# untitled.net
KiCad netlist of a schematic drawn in EAGLE
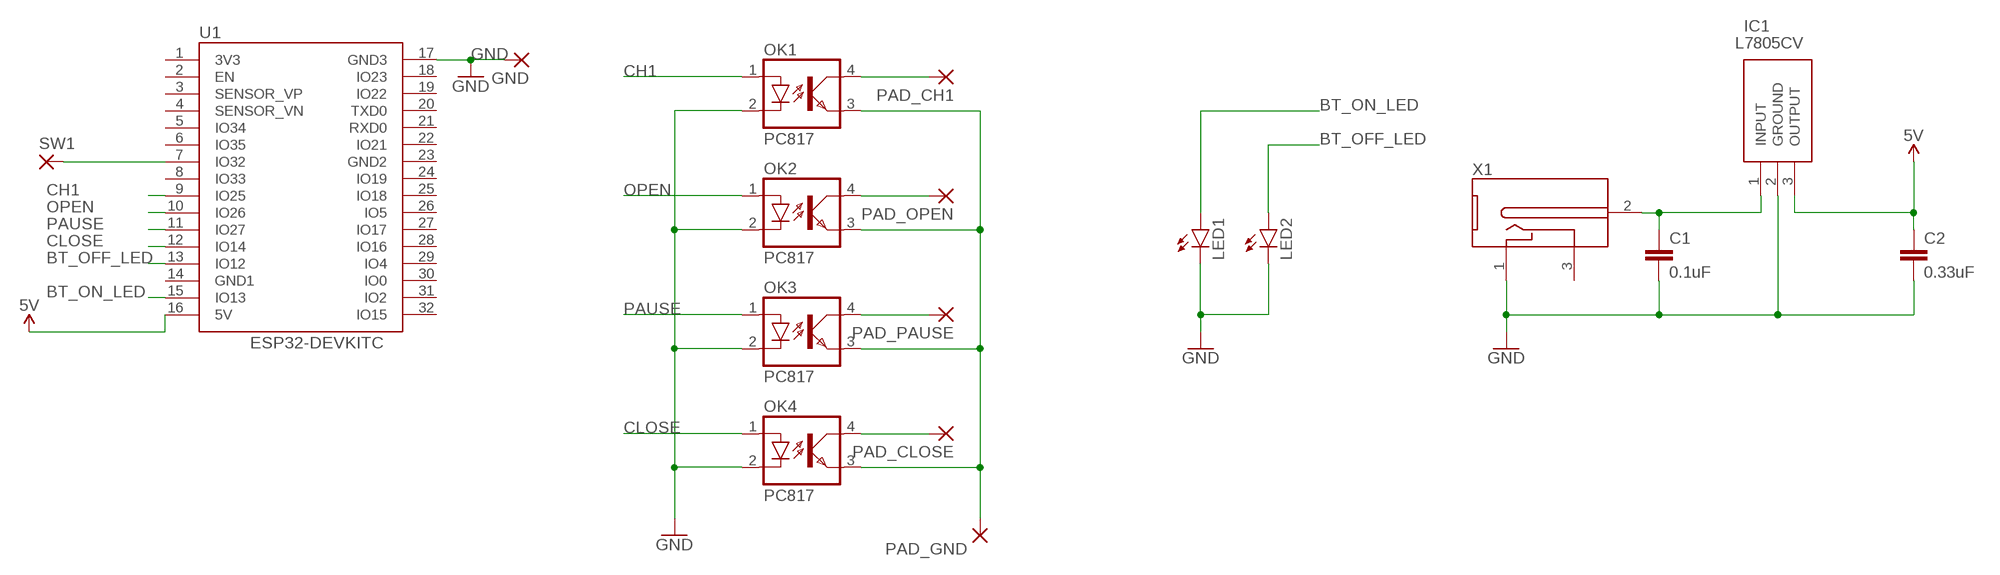
[diagram p0: schematic, sheet 1]

(export (version "E")
  (design (tool "Eeschema 10.0.6"))
  (components
    (comp (ref "C1")
      (value "0.1uF")
      (footprint "eagle-import:C2.5-2")
      (libsource (lib "eagle-import") (part "C2.5/2"))
    )
    (comp (ref "C2")
      (value "0.33uF")
      (footprint "eagle-import:C2.5-2")
      (libsource (lib "eagle-import") (part "C2.5/2"))
    )
    (comp (ref "GND")
      (value "2,54/1,0")
      (footprint "eagle-import:2,54_1,0")
      (libsource (lib "eagle-import") (part "2,54/1,0"))
    )
    (comp (ref "IC1")
      (value "L7805CV")
      (footprint "eagle-import:TO255P460X1020X2008-3P")
      (fields (field (name "MOUSER_PART_NUMBER") "511-L7805CV"))
      (libsource (lib "eagle-import") (part "L7805CV"))
    )
    (comp (ref "LED1")
      (value "LED5MM")
      (footprint "eagle-import:LED5MM")
      (libsource (lib "eagle-import") (part "LED5MM"))
    )
    (comp (ref "LED2")
      (value "LED5MM")
      (footprint "eagle-import:LED5MM")
      (libsource (lib "eagle-import") (part "LED5MM"))
    )
    (comp (ref "OK1")
      (value "PC817")
      (footprint "eagle-import:DIL04")
      (fields (field (name "MPN") "PC817X4J000F"))
      (libsource (lib "eagle-import") (part "PC817"))
    )
    (comp (ref "OK2")
      (value "PC817")
      (footprint "eagle-import:DIL04")
      (fields (field (name "MPN") "PC817X4J000F"))
      (libsource (lib "eagle-import") (part "PC817"))
    )
    (comp (ref "OK3")
      (value "PC817")
      (footprint "eagle-import:DIL04")
      (fields (field (name "MPN") "PC817X4J000F"))
      (libsource (lib "eagle-import") (part "PC817"))
    )
    (comp (ref "OK4")
      (value "PC817")
      (footprint "eagle-import:DIL04")
      (fields (field (name "MPN") "PC817X4J000F"))
      (libsource (lib "eagle-import") (part "PC817"))
    )
    (comp (ref "PAD_CH1")
      (value "2,54/1,0")
      (footprint "eagle-import:2,54_1,0")
      (libsource (lib "eagle-import") (part "2,54/1,0"))
    )
    (comp (ref "PAD_CLOSE")
      (value "2,54/1,0")
      (footprint "eagle-import:2,54_1,0")
      (libsource (lib "eagle-import") (part "2,54/1,0"))
    )
    (comp (ref "PAD_GND")
      (value "2,54/1,0")
      (footprint "eagle-import:2,54_1,0")
      (libsource (lib "eagle-import") (part "2,54/1,0"))
    )
    (comp (ref "PAD_OPEN")
      (value "2,54/1,0")
      (footprint "eagle-import:2,54_1,0")
      (libsource (lib "eagle-import") (part "2,54/1,0"))
    )
    (comp (ref "PAD_PAUSE")
      (value "2,54/1,0")
      (footprint "eagle-import:2,54_1,0")
      (libsource (lib "eagle-import") (part "2,54/1,0"))
    )
    (comp (ref "SW1")
      (value "2,54/1,0")
      (footprint "eagle-import:2,54_1,0")
      (libsource (lib "eagle-import") (part "2,54/1,0"))
    )
    (comp (ref "U1")
      (value "ESP32-DEVKITC")
      (footprint "eagle-import:MODULE_ESP32-DEVKITC")
      (fields (field (name "MF") "Espressif Systems"))
      (libsource (lib "eagle-import") (part "ESP32-DEVKITC"))
    )
    (comp (ref "X1")
      (value "DC-2.1MM-5MM")
      (footprint "eagle-import:DC-21MM")
      (libsource (lib "eagle-import") (part "DC-5MM-2.1MM"))
    )
  )
  (nets
    (net (code "1") (name "/2") (class "Default")
      (node (ref "X1") (pin "3") (pinfunction "2_3") (pintype "power_in"))
    )
    (net (code "2") (name "/3V3") (class "Default")
      (node (ref "U1") (pin "1") (pinfunction "3V3_1") (pintype "power_in"))
    )
    (net (code "3") (name "/BT_OFF_LED") (class "Default")
      (node (ref "LED2") (pin "A") (pinfunction "A_A") (pintype "passive"))
      (node (ref "U1") (pin "13") (pinfunction "IO12_13") (pintype "bidirectional"))
    )
    (net (code "4") (name "/BT_ON_LED") (class "Default")
      (node (ref "LED1") (pin "A") (pinfunction "A_A") (pintype "passive"))
      (node (ref "U1") (pin "15") (pinfunction "IO13_15") (pintype "bidirectional"))
    )
    (net (code "5") (name "/CH1") (class "Default")
      (node (ref "OK1") (pin "1") (pinfunction "A_1") (pintype "passive"))
      (node (ref "U1") (pin "9") (pinfunction "IO25_9") (pintype "bidirectional"))
    )
    (net (code "6") (name "/CLOSE") (class "Default")
      (node (ref "OK4") (pin "1") (pinfunction "A_1") (pintype "passive"))
      (node (ref "U1") (pin "12") (pinfunction "IO14_12") (pintype "bidirectional"))
    )
    (net (code "7") (name "/GND1") (class "Default")
      (node (ref "U1") (pin "14") (pinfunction "GND1_14") (pintype "power_in"))
    )
    (net (code "8") (name "/GND2") (class "Default")
      (node (ref "U1") (pin "23") (pinfunction "GND2_23") (pintype "power_in"))
    )
    (net (code "9") (name "/OPEN") (class "Default")
      (node (ref "OK2") (pin "1") (pinfunction "A_1") (pintype "passive"))
      (node (ref "U1") (pin "10") (pinfunction "IO26_10") (pintype "bidirectional"))
    )
    (net (code "10") (name "/PAUSE") (class "Default")
      (node (ref "OK3") (pin "1") (pinfunction "A_1") (pintype "passive"))
      (node (ref "U1") (pin "11") (pinfunction "IO27_11") (pintype "bidirectional"))
    )
    (net (code "11") (name "5V") (class "Default")
      (node (ref "C2") (pin "1") (pinfunction "1_1") (pintype "passive"))
      (node (ref "IC1") (pin "3") (pinfunction "OUTPUT_3") (pintype "bidirectional"))
      (node (ref "U1") (pin "16") (pinfunction "5V_16") (pintype "bidirectional"))
    )
    (net (code "12") (name "GND") (class "Default")
      (node (ref "C1") (pin "2") (pinfunction "2_2") (pintype "passive"))
      (node (ref "C2") (pin "2") (pinfunction "2_2") (pintype "passive"))
      (node (ref "GND") (pin "1") (pinfunction "P_1") (pintype "passive"))
      (node (ref "IC1") (pin "2") (pinfunction "GROUND_2") (pintype "bidirectional"))
      (node (ref "LED1") (pin "K") (pinfunction "C_K") (pintype "passive"))
      (node (ref "LED2") (pin "K") (pinfunction "C_K") (pintype "passive"))
      (node (ref "OK1") (pin "2") (pinfunction "C_2") (pintype "passive"))
      (node (ref "OK2") (pin "2") (pinfunction "C_2") (pintype "passive"))
      (node (ref "OK3") (pin "2") (pinfunction "C_2") (pintype "passive"))
      (node (ref "OK4") (pin "2") (pinfunction "C_2") (pintype "passive"))
      (node (ref "U1") (pin "17") (pinfunction "GND3_17") (pintype "power_in"))
      (node (ref "X1") (pin "1") (pinfunction "1_1") (pintype "power_in"))
    )
    (net (code "13") (name "Net-(IC1-INPUT)") (class "Default")
      (node (ref "C1") (pin "1") (pinfunction "1_1") (pintype "passive"))
      (node (ref "IC1") (pin "1") (pinfunction "INPUT_1") (pintype "bidirectional"))
      (node (ref "X1") (pin "2") (pinfunction "3_2") (pintype "power_in"))
    )
    (net (code "14") (name "Net-(OK1-COL)") (class "Default")
      (node (ref "OK1") (pin "4") (pinfunction "COL_4") (pintype "passive"))
      (node (ref "PAD_CH1") (pin "1") (pinfunction "P_1") (pintype "passive"))
    )
    (net (code "15") (name "Net-(OK1-EMIT)") (class "Default")
      (node (ref "OK1") (pin "3") (pinfunction "EMIT_3") (pintype "passive"))
      (node (ref "OK2") (pin "3") (pinfunction "EMIT_3") (pintype "passive"))
      (node (ref "OK3") (pin "3") (pinfunction "EMIT_3") (pintype "passive"))
      (node (ref "OK4") (pin "3") (pinfunction "EMIT_3") (pintype "passive"))
      (node (ref "PAD_GND") (pin "1") (pinfunction "P_1") (pintype "passive"))
    )
    (net (code "16") (name "Net-(OK2-COL)") (class "Default")
      (node (ref "OK2") (pin "4") (pinfunction "COL_4") (pintype "passive"))
      (node (ref "PAD_OPEN") (pin "1") (pinfunction "P_1") (pintype "passive"))
    )
    (net (code "17") (name "Net-(OK3-COL)") (class "Default")
      (node (ref "OK3") (pin "4") (pinfunction "COL_4") (pintype "passive"))
      (node (ref "PAD_PAUSE") (pin "1") (pinfunction "P_1") (pintype "passive"))
    )
    (net (code "18") (name "Net-(OK4-COL)") (class "Default")
      (node (ref "OK4") (pin "4") (pinfunction "COL_4") (pintype "passive"))
      (node (ref "PAD_CLOSE") (pin "1") (pinfunction "P_1") (pintype "passive"))
    )
    (net (code "19") (name "Net-(SW1-P)") (class "Default")
      (node (ref "SW1") (pin "1") (pinfunction "P_1") (pintype "passive"))
      (node (ref "U1") (pin "7") (pinfunction "IO32_7") (pintype "bidirectional"))
    )
    (net (code "20") (name "unconnected-(U1-EN-Pad2)") (class "Default")
      (node (ref "U1") (pin "2") (pinfunction "EN_2") (pintype "input"))
    )
    (net (code "21") (name "unconnected-(U1-IO0-Pad30)") (class "Default")
      (node (ref "U1") (pin "30") (pinfunction "IO0_30") (pintype "bidirectional"))
    )
    (net (code "22") (name "unconnected-(U1-IO2-Pad31)") (class "Default")
      (node (ref "U1") (pin "31") (pinfunction "IO2_31") (pintype "bidirectional"))
    )
    (net (code "23") (name "unconnected-(U1-IO4-Pad29)") (class "Default")
      (node (ref "U1") (pin "29") (pinfunction "IO4_29") (pintype "bidirectional"))
    )
    (net (code "24") (name "unconnected-(U1-IO5-Pad26)") (class "Default")
      (node (ref "U1") (pin "26") (pinfunction "IO5_26") (pintype "bidirectional"))
    )
    (net (code "25") (name "unconnected-(U1-IO15-Pad32)") (class "Default")
      (node (ref "U1") (pin "32") (pinfunction "IO15_32") (pintype "bidirectional"))
    )
    (net (code "26") (name "unconnected-(U1-IO16-Pad28)") (class "Default")
      (node (ref "U1") (pin "28") (pinfunction "IO16_28") (pintype "bidirectional"))
    )
    (net (code "27") (name "unconnected-(U1-IO17-Pad27)") (class "Default")
      (node (ref "U1") (pin "27") (pinfunction "IO17_27") (pintype "bidirectional"))
    )
    (net (code "28") (name "unconnected-(U1-IO18-Pad25)") (class "Default")
      (node (ref "U1") (pin "25") (pinfunction "IO18_25") (pintype "bidirectional"))
    )
    (net (code "29") (name "unconnected-(U1-IO19-Pad24)") (class "Default")
      (node (ref "U1") (pin "24") (pinfunction "IO19_24") (pintype "bidirectional"))
    )
    (net (code "30") (name "unconnected-(U1-IO21-Pad22)") (class "Default")
      (node (ref "U1") (pin "22") (pinfunction "IO21_22") (pintype "bidirectional"))
    )
    (net (code "31") (name "unconnected-(U1-IO22-Pad19)") (class "Default")
      (node (ref "U1") (pin "19") (pinfunction "IO22_19") (pintype "bidirectional"))
    )
    (net (code "32") (name "unconnected-(U1-IO23-Pad18)") (class "Default")
      (node (ref "U1") (pin "18") (pinfunction "IO23_18") (pintype "bidirectional"))
    )
    (net (code "33") (name "unconnected-(U1-IO33-Pad8)") (class "Default")
      (node (ref "U1") (pin "8") (pinfunction "IO33_8") (pintype "bidirectional"))
    )
    (net (code "34") (name "unconnected-(U1-IO34-Pad5)") (class "Default")
      (node (ref "U1") (pin "5") (pinfunction "IO34_5") (pintype "bidirectional"))
    )
    (net (code "35") (name "unconnected-(U1-IO35-Pad6)") (class "Default")
      (node (ref "U1") (pin "6") (pinfunction "IO35_6") (pintype "bidirectional"))
    )
    (net (code "36") (name "unconnected-(U1-RXD0-Pad21)") (class "Default")
      (node (ref "U1") (pin "21") (pinfunction "RXD0_21") (pintype "input"))
    )
    (net (code "37") (name "unconnected-(U1-SENSOR_VN-Pad4)") (class "Default")
      (node (ref "U1") (pin "4") (pinfunction "SENSOR_VN_4") (pintype "input"))
    )
    (net (code "38") (name "unconnected-(U1-SENSOR_VP-Pad3)") (class "Default")
      (node (ref "U1") (pin "3") (pinfunction "SENSOR_VP_3") (pintype "input"))
    )
    (net (code "39") (name "unconnected-(U1-TXD0-Pad20)") (class "Default")
      (node (ref "U1") (pin "20") (pinfunction "TXD0_20") (pintype "output"))
    )
  )
)
